# 11_FlashMemory.net
KiCad netlist of a schematic drawn in Altium Designer
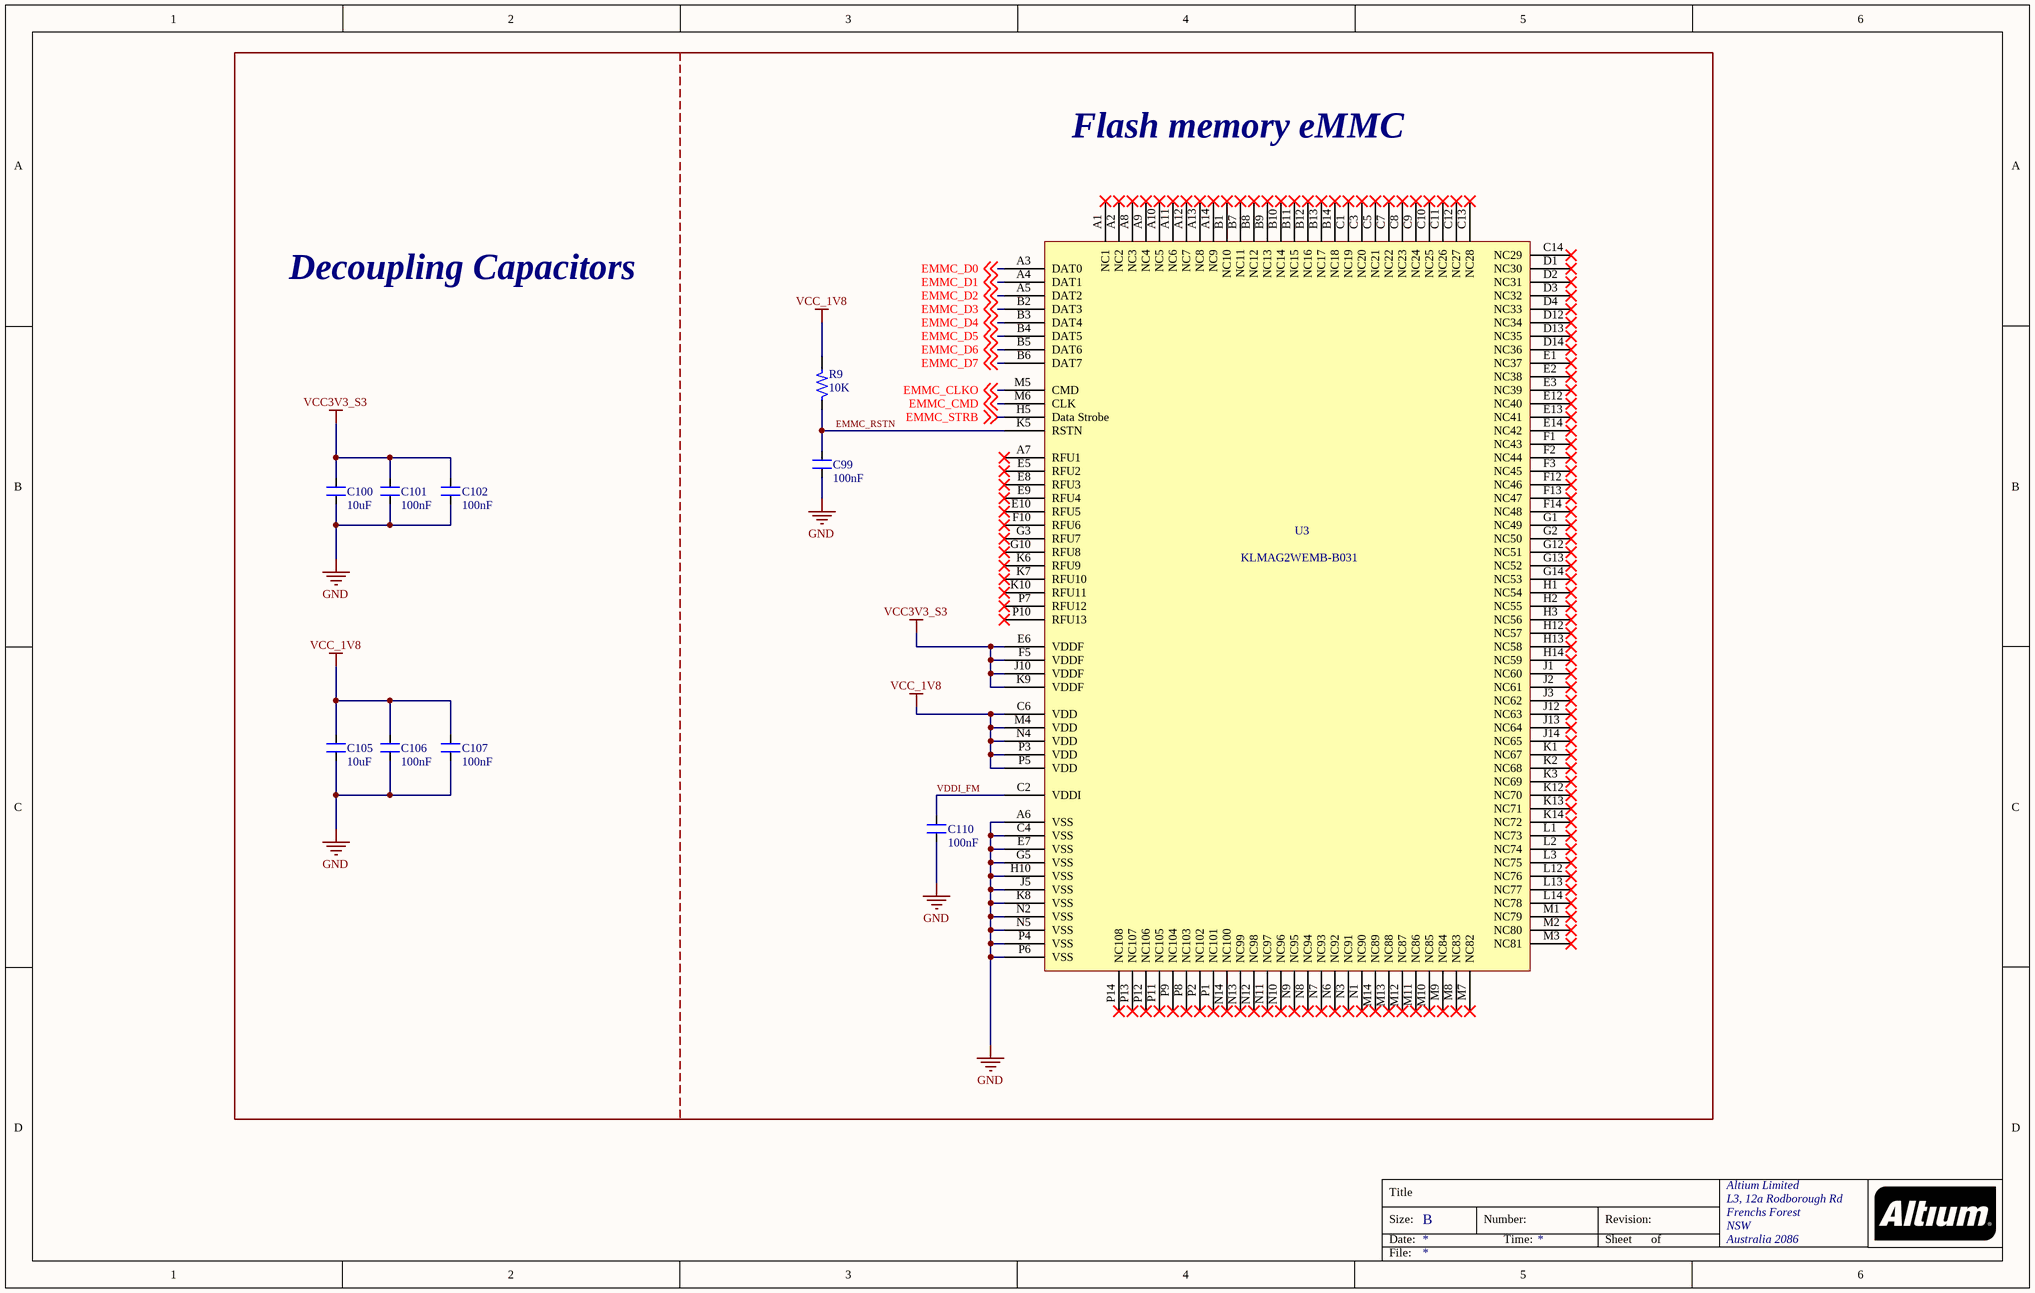
[diagram p0: [11] FlashMemory.SchDoc]

(export (version "E")
  (design (tool "Eeschema 10.0.6"))
  (components
    (comp (ref "C99")
      (value "100nF")
      (footprint "CAP_0201")
      (description "0.1µF ±10% 25V Ceramic Capacitor X5R 0201 (0603 Metric)")
      (fields
        (field (name "MANUFACTURER") "TDK Corporation")
        (field (name "MANUFACTURER PART NUMBER") "C0603X5R1E104K030BB")
      )
      (libsource (lib "EsteemPCB_SOM_Course_intlib") (part "CAP_100nF-25V-10%-0201"))
    )
    (comp (ref "C100")
      (value "10uF")
      (footprint "CAP_0603")
      (description "10µF ±10% 25V Ceramic Capacitor X5R 0603 (1608 Metric)")
      (fields
        (field (name "MANUFACTURER") "Murata Electronics")
        (field (name "MANUFACTURER PART NUMBER") "GRM188R61E106KA73D")
      )
      (libsource (lib "EsteemPCB_SOM_Course_intlib") (part "CAP_10uF-25V-10%-0603"))
    )
    (comp (ref "C101")
      (value "100nF")
      (footprint "CAP_0201")
      (description "0.1µF ±10% 25V Ceramic Capacitor X5R 0201 (0603 Metric)")
      (fields
        (field (name "MANUFACTURER") "TDK Corporation")
        (field (name "MANUFACTURER PART NUMBER") "C0603X5R1E104K030BB")
      )
      (libsource (lib "EsteemPCB_SOM_Course_intlib") (part "CAP_100nF-25V-10%-0201"))
    )
    (comp (ref "C102")
      (value "100nF")
      (footprint "CAP_0201")
      (description "0.1µF ±10% 25V Ceramic Capacitor X5R 0201 (0603 Metric)")
      (fields
        (field (name "MANUFACTURER") "TDK Corporation")
        (field (name "MANUFACTURER PART NUMBER") "C0603X5R1E104K030BB")
      )
      (libsource (lib "EsteemPCB_SOM_Course_intlib") (part "CAP_100nF-25V-10%-0201"))
    )
    (comp (ref "C105")
      (value "10uF")
      (footprint "CAP_0603")
      (description "10µF ±10% 25V Ceramic Capacitor X5R 0603 (1608 Metric)")
      (fields
        (field (name "MANUFACTURER") "Murata Electronics")
        (field (name "MANUFACTURER PART NUMBER") "GRM188R61E106KA73D")
      )
      (libsource (lib "EsteemPCB_SOM_Course_intlib") (part "CAP_10uF-25V-10%-0603"))
    )
    (comp (ref "C106")
      (value "100nF")
      (footprint "CAP_0201")
      (description "0.1µF ±10% 25V Ceramic Capacitor X5R 0201 (0603 Metric)")
      (fields
        (field (name "MANUFACTURER") "TDK Corporation")
        (field (name "MANUFACTURER PART NUMBER") "C0603X5R1E104K030BB")
      )
      (libsource (lib "EsteemPCB_SOM_Course_intlib") (part "CAP_100nF-25V-10%-0201"))
    )
    (comp (ref "C107")
      (value "100nF")
      (footprint "CAP_0201")
      (description "0.1µF ±10% 25V Ceramic Capacitor X5R 0201 (0603 Metric)")
      (fields
        (field (name "MANUFACTURER") "TDK Corporation")
        (field (name "MANUFACTURER PART NUMBER") "C0603X5R1E104K030BB")
      )
      (libsource (lib "EsteemPCB_SOM_Course_intlib") (part "CAP_100nF-25V-10%-0201"))
    )
    (comp (ref "C110")
      (value "100nF")
      (footprint "CAP_0201")
      (description "0.1µF ±10% 25V Ceramic Capacitor X5R 0201 (0603 Metric)")
      (fields
        (field (name "MANUFACTURER") "TDK Corporation")
        (field (name "MANUFACTURER PART NUMBER") "C0603X5R1E104K030BB")
      )
      (libsource (lib "EsteemPCB_SOM_Course_intlib") (part "CAP_100nF-25V-10%-0201"))
    )
    (comp (ref "R9")
      (value "10K")
      (footprint "RES_0201")
      (description "10 kOhms ±1% 0.05W, 1/20W Chip Resistor 0201 (0603 Metric) Thick Film")
      (fields
        (field (name "MANUFACTURER") "Stackpole Electronics Inc")
        (field (name "MANUFACTURER PART NUMBER") "RMCF0201FT10K0")
      )
      (libsource (lib "EsteemPCB_SOM_Course_intlib") (part "RES_10K-0.05W-1%-0201"))
    )
    (comp (ref "U3")
      (value "KLMAG2WEMB-B031")
      (footprint "BGA153C50P14X14_1150X1300X70")
      (description "16GB NAND Flash Memory")
      (fields (field (name "MANUFACTURER") "Samsung Electronics"))
      (libsource (lib "EsteemPCB_SOM_Course_intlib") (part "IC_KLMAG2WEMB-B031"))
    )
  )
  (nets
    (net (code "1") (name "/EMMC_RSTN") (class "Default")
      (node (ref "C99") (pin "2") (pinfunction "2_2") (pintype "passive"))
      (node (ref "R9") (pin "1") (pinfunction "1_1") (pintype "passive"))
      (node (ref "U3") (pin "K5") (pinfunction "RSTN_K5") (pintype "passive"))
    )
    (net (code "2") (name "/VDDI_FM") (class "Default")
      (node (ref "C110") (pin "2") (pinfunction "2_2") (pintype "passive"))
      (node (ref "U3") (pin "C2") (pinfunction "VDDI_C2") (pintype "passive"))
    )
    (net (code "3") (name "EMMC_CLKO") (class "Default")
      (node (ref "U3") (pin "M5") (pinfunction "CMD_M5") (pintype "passive"))
    )
    (net (code "4") (name "EMMC_CMD") (class "Default")
      (node (ref "U3") (pin "M6") (pinfunction "CLK_M6") (pintype "passive"))
    )
    (net (code "5") (name "EMMC_D0") (class "Default")
      (node (ref "U3") (pin "A3") (pinfunction "DAT0_A3") (pintype "passive"))
    )
    (net (code "6") (name "EMMC_D1") (class "Default")
      (node (ref "U3") (pin "A4") (pinfunction "DAT1_A4") (pintype "passive"))
    )
    (net (code "7") (name "EMMC_D2") (class "Default")
      (node (ref "U3") (pin "A5") (pinfunction "DAT2_A5") (pintype "passive"))
    )
    (net (code "8") (name "EMMC_D3") (class "Default")
      (node (ref "U3") (pin "B2") (pinfunction "DAT3_B2") (pintype "passive"))
    )
    (net (code "9") (name "EMMC_D4") (class "Default")
      (node (ref "U3") (pin "B3") (pinfunction "DAT4_B3") (pintype "passive"))
    )
    (net (code "10") (name "EMMC_D5") (class "Default")
      (node (ref "U3") (pin "B4") (pinfunction "DAT5_B4") (pintype "passive"))
    )
    (net (code "11") (name "EMMC_D6") (class "Default")
      (node (ref "U3") (pin "B5") (pinfunction "DAT6_B5") (pintype "passive"))
    )
    (net (code "12") (name "EMMC_D7") (class "Default")
      (node (ref "U3") (pin "B6") (pinfunction "DAT7_B6") (pintype "passive"))
    )
    (net (code "13") (name "EMMC_STRB") (class "Default")
      (node (ref "U3") (pin "H5") (pinfunction "Data_Strobe_H5") (pintype "passive"))
    )
    (net (code "14") (name "GND") (class "Default")
      (node (ref "C100") (pin "1") (pinfunction "1_1") (pintype "passive"))
      (node (ref "C101") (pin "1") (pinfunction "1_1") (pintype "passive"))
      (node (ref "C102") (pin "1") (pinfunction "1_1") (pintype "passive"))
      (node (ref "C105") (pin "1") (pinfunction "1_1") (pintype "passive"))
      (node (ref "C106") (pin "1") (pinfunction "1_1") (pintype "passive"))
      (node (ref "C107") (pin "1") (pinfunction "1_1") (pintype "passive"))
      (node (ref "C110") (pin "1") (pinfunction "1_1") (pintype "passive"))
      (node (ref "C99") (pin "1") (pinfunction "1_1") (pintype "passive"))
      (node (ref "U3") (pin "A6") (pinfunction "VSS_A6") (pintype "passive"))
      (node (ref "U3") (pin "C4") (pinfunction "VSS_C4") (pintype "passive"))
      (node (ref "U3") (pin "E7") (pinfunction "VSS_E7") (pintype "passive"))
      (node (ref "U3") (pin "G5") (pinfunction "VSS_G5") (pintype "passive"))
      (node (ref "U3") (pin "H10") (pinfunction "VSS_H10") (pintype "passive"))
      (node (ref "U3") (pin "J5") (pinfunction "VSS_J5") (pintype "passive"))
      (node (ref "U3") (pin "K8") (pinfunction "VSS_K8") (pintype "passive"))
      (node (ref "U3") (pin "N2") (pinfunction "VSS_N2") (pintype "passive"))
      (node (ref "U3") (pin "N5") (pinfunction "VSS_N5") (pintype "passive"))
      (node (ref "U3") (pin "P4") (pinfunction "VSS_P4") (pintype "passive"))
      (node (ref "U3") (pin "P6") (pinfunction "VSS_P6") (pintype "passive"))
    )
    (net (code "15") (name "VCC3V3_S3") (class "Default")
      (node (ref "C100") (pin "2") (pinfunction "2_2") (pintype "passive"))
      (node (ref "C101") (pin "2") (pinfunction "2_2") (pintype "passive"))
      (node (ref "C102") (pin "2") (pinfunction "2_2") (pintype "passive"))
      (node (ref "U3") (pin "E6") (pinfunction "VDDF_E6") (pintype "passive"))
      (node (ref "U3") (pin "F5") (pinfunction "VDDF_F5") (pintype "passive"))
      (node (ref "U3") (pin "J10") (pinfunction "VDDF_J10") (pintype "passive"))
      (node (ref "U3") (pin "K9") (pinfunction "VDDF_K9") (pintype "passive"))
    )
    (net (code "16") (name "VCC_1V8") (class "Default")
      (node (ref "C105") (pin "2") (pinfunction "2_2") (pintype "passive"))
      (node (ref "C106") (pin "2") (pinfunction "2_2") (pintype "passive"))
      (node (ref "C107") (pin "2") (pinfunction "2_2") (pintype "passive"))
      (node (ref "R9") (pin "2") (pinfunction "2_2") (pintype "passive"))
      (node (ref "U3") (pin "C6") (pinfunction "VDD_C6") (pintype "passive"))
      (node (ref "U3") (pin "M4") (pinfunction "VDD_M4") (pintype "passive"))
      (node (ref "U3") (pin "N4") (pinfunction "VDD_N4") (pintype "passive"))
      (node (ref "U3") (pin "P3") (pinfunction "VDD_P3") (pintype "passive"))
      (node (ref "U3") (pin "P5") (pinfunction "VDD_P5") (pintype "passive"))
    )
    (net (code "17") (name "unconnected-(U3-NC1-PadA1)") (class "Default")
      (node (ref "U3") (pin "A1") (pinfunction "NC1_A1") (pintype "passive+no_connect"))
    )
    (net (code "18") (name "unconnected-(U3-NC2-PadA2)") (class "Default")
      (node (ref "U3") (pin "A2") (pinfunction "NC2_A2") (pintype "passive+no_connect"))
    )
    (net (code "19") (name "unconnected-(U3-NC3-PadA8)") (class "Default")
      (node (ref "U3") (pin "A8") (pinfunction "NC3_A8") (pintype "passive+no_connect"))
    )
    (net (code "20") (name "unconnected-(U3-NC4-PadA9)") (class "Default")
      (node (ref "U3") (pin "A9") (pinfunction "NC4_A9") (pintype "passive+no_connect"))
    )
    (net (code "21") (name "unconnected-(U3-NC5-PadA10)") (class "Default")
      (node (ref "U3") (pin "A10") (pinfunction "NC5_A10") (pintype "passive+no_connect"))
    )
    (net (code "22") (name "unconnected-(U3-NC6-PadA11)") (class "Default")
      (node (ref "U3") (pin "A11") (pinfunction "NC6_A11") (pintype "passive+no_connect"))
    )
    (net (code "23") (name "unconnected-(U3-NC7-PadA12)") (class "Default")
      (node (ref "U3") (pin "A12") (pinfunction "NC7_A12") (pintype "passive+no_connect"))
    )
    (net (code "24") (name "unconnected-(U3-NC8-PadA13)") (class "Default")
      (node (ref "U3") (pin "A13") (pinfunction "NC8_A13") (pintype "passive+no_connect"))
    )
    (net (code "25") (name "unconnected-(U3-NC9-PadA14)") (class "Default")
      (node (ref "U3") (pin "A14") (pinfunction "NC9_A14") (pintype "passive+no_connect"))
    )
    (net (code "26") (name "unconnected-(U3-NC10-PadB1)") (class "Default")
      (node (ref "U3") (pin "B1") (pinfunction "NC10_B1") (pintype "passive+no_connect"))
    )
    (net (code "27") (name "unconnected-(U3-NC11-PadB7)") (class "Default")
      (node (ref "U3") (pin "B7") (pinfunction "NC11_B7") (pintype "passive+no_connect"))
    )
    (net (code "28") (name "unconnected-(U3-NC12-PadB8)") (class "Default")
      (node (ref "U3") (pin "B8") (pinfunction "NC12_B8") (pintype "passive+no_connect"))
    )
    (net (code "29") (name "unconnected-(U3-NC13-PadB9)") (class "Default")
      (node (ref "U3") (pin "B9") (pinfunction "NC13_B9") (pintype "passive+no_connect"))
    )
    (net (code "30") (name "unconnected-(U3-NC14-PadB10)") (class "Default")
      (node (ref "U3") (pin "B10") (pinfunction "NC14_B10") (pintype "passive+no_connect"))
    )
    (net (code "31") (name "unconnected-(U3-NC15-PadB11)") (class "Default")
      (node (ref "U3") (pin "B11") (pinfunction "NC15_B11") (pintype "passive+no_connect"))
    )
    (net (code "32") (name "unconnected-(U3-NC16-PadB12)") (class "Default")
      (node (ref "U3") (pin "B12") (pinfunction "NC16_B12") (pintype "passive+no_connect"))
    )
    (net (code "33") (name "unconnected-(U3-NC17-PadB13)") (class "Default")
      (node (ref "U3") (pin "B13") (pinfunction "NC17_B13") (pintype "passive+no_connect"))
    )
    (net (code "34") (name "unconnected-(U3-NC18-PadB14)") (class "Default")
      (node (ref "U3") (pin "B14") (pinfunction "NC18_B14") (pintype "passive+no_connect"))
    )
    (net (code "35") (name "unconnected-(U3-NC19-PadC1)") (class "Default")
      (node (ref "U3") (pin "C1") (pinfunction "NC19_C1") (pintype "passive+no_connect"))
    )
    (net (code "36") (name "unconnected-(U3-NC20-PadC3)") (class "Default")
      (node (ref "U3") (pin "C3") (pinfunction "NC20_C3") (pintype "passive+no_connect"))
    )
    (net (code "37") (name "unconnected-(U3-NC21-PadC5)") (class "Default")
      (node (ref "U3") (pin "C5") (pinfunction "NC21_C5") (pintype "passive+no_connect"))
    )
    (net (code "38") (name "unconnected-(U3-NC22-PadC7)") (class "Default")
      (node (ref "U3") (pin "C7") (pinfunction "NC22_C7") (pintype "passive+no_connect"))
    )
    (net (code "39") (name "unconnected-(U3-NC23-PadC8)") (class "Default")
      (node (ref "U3") (pin "C8") (pinfunction "NC23_C8") (pintype "passive+no_connect"))
    )
    (net (code "40") (name "unconnected-(U3-NC24-PadC9)") (class "Default")
      (node (ref "U3") (pin "C9") (pinfunction "NC24_C9") (pintype "passive+no_connect"))
    )
    (net (code "41") (name "unconnected-(U3-NC25-PadC10)") (class "Default")
      (node (ref "U3") (pin "C10") (pinfunction "NC25_C10") (pintype "passive+no_connect"))
    )
    (net (code "42") (name "unconnected-(U3-NC26-PadC11)") (class "Default")
      (node (ref "U3") (pin "C11") (pinfunction "NC26_C11") (pintype "passive+no_connect"))
    )
    (net (code "43") (name "unconnected-(U3-NC27-PadC12)") (class "Default")
      (node (ref "U3") (pin "C12") (pinfunction "NC27_C12") (pintype "passive+no_connect"))
    )
    (net (code "44") (name "unconnected-(U3-NC28-PadC13)") (class "Default")
      (node (ref "U3") (pin "C13") (pinfunction "NC28_C13") (pintype "passive+no_connect"))
    )
    (net (code "45") (name "unconnected-(U3-NC29-PadC14)") (class "Default")
      (node (ref "U3") (pin "C14") (pinfunction "NC29_C14") (pintype "passive+no_connect"))
    )
    (net (code "46") (name "unconnected-(U3-NC30-PadD1)") (class "Default")
      (node (ref "U3") (pin "D1") (pinfunction "NC30_D1") (pintype "passive+no_connect"))
    )
    (net (code "47") (name "unconnected-(U3-NC31-PadD2)") (class "Default")
      (node (ref "U3") (pin "D2") (pinfunction "NC31_D2") (pintype "passive+no_connect"))
    )
    (net (code "48") (name "unconnected-(U3-NC32-PadD3)") (class "Default")
      (node (ref "U3") (pin "D3") (pinfunction "NC32_D3") (pintype "passive+no_connect"))
    )
    (net (code "49") (name "unconnected-(U3-NC33-PadD4)") (class "Default")
      (node (ref "U3") (pin "D4") (pinfunction "NC33_D4") (pintype "passive+no_connect"))
    )
    (net (code "50") (name "unconnected-(U3-NC34-PadD12)") (class "Default")
      (node (ref "U3") (pin "D12") (pinfunction "NC34_D12") (pintype "passive+no_connect"))
    )
    (net (code "51") (name "unconnected-(U3-NC35-PadD13)") (class "Default")
      (node (ref "U3") (pin "D13") (pinfunction "NC35_D13") (pintype "passive+no_connect"))
    )
    (net (code "52") (name "unconnected-(U3-NC36-PadD14)") (class "Default")
      (node (ref "U3") (pin "D14") (pinfunction "NC36_D14") (pintype "passive+no_connect"))
    )
    (net (code "53") (name "unconnected-(U3-NC37-PadE1)") (class "Default")
      (node (ref "U3") (pin "E1") (pinfunction "NC37_E1") (pintype "passive+no_connect"))
    )
    (net (code "54") (name "unconnected-(U3-NC38-PadE2)") (class "Default")
      (node (ref "U3") (pin "E2") (pinfunction "NC38_E2") (pintype "passive+no_connect"))
    )
    (net (code "55") (name "unconnected-(U3-NC39-PadE3)") (class "Default")
      (node (ref "U3") (pin "E3") (pinfunction "NC39_E3") (pintype "passive+no_connect"))
    )
    (net (code "56") (name "unconnected-(U3-NC40-PadE12)") (class "Default")
      (node (ref "U3") (pin "E12") (pinfunction "NC40_E12") (pintype "passive+no_connect"))
    )
    (net (code "57") (name "unconnected-(U3-NC41-PadE13)") (class "Default")
      (node (ref "U3") (pin "E13") (pinfunction "NC41_E13") (pintype "passive+no_connect"))
    )
    (net (code "58") (name "unconnected-(U3-NC42-PadE14)") (class "Default")
      (node (ref "U3") (pin "E14") (pinfunction "NC42_E14") (pintype "passive+no_connect"))
    )
    (net (code "59") (name "unconnected-(U3-NC43-PadF1)") (class "Default")
      (node (ref "U3") (pin "F1") (pinfunction "NC43_F1") (pintype "passive+no_connect"))
    )
    (net (code "60") (name "unconnected-(U3-NC44-PadF2)") (class "Default")
      (node (ref "U3") (pin "F2") (pinfunction "NC44_F2") (pintype "passive+no_connect"))
    )
    (net (code "61") (name "unconnected-(U3-NC45-PadF3)") (class "Default")
      (node (ref "U3") (pin "F3") (pinfunction "NC45_F3") (pintype "passive+no_connect"))
    )
    (net (code "62") (name "unconnected-(U3-NC46-PadF12)") (class "Default")
      (node (ref "U3") (pin "F12") (pinfunction "NC46_F12") (pintype "passive+no_connect"))
    )
    (net (code "63") (name "unconnected-(U3-NC47-PadF13)") (class "Default")
      (node (ref "U3") (pin "F13") (pinfunction "NC47_F13") (pintype "passive+no_connect"))
    )
    (net (code "64") (name "unconnected-(U3-NC48-PadF14)") (class "Default")
      (node (ref "U3") (pin "F14") (pinfunction "NC48_F14") (pintype "passive+no_connect"))
    )
    (net (code "65") (name "unconnected-(U3-NC49-PadG1)") (class "Default")
      (node (ref "U3") (pin "G1") (pinfunction "NC49_G1") (pintype "passive+no_connect"))
    )
    (net (code "66") (name "unconnected-(U3-NC50-PadG2)") (class "Default")
      (node (ref "U3") (pin "G2") (pinfunction "NC50_G2") (pintype "passive+no_connect"))
    )
    (net (code "67") (name "unconnected-(U3-NC51-PadG12)") (class "Default")
      (node (ref "U3") (pin "G12") (pinfunction "NC51_G12") (pintype "passive+no_connect"))
    )
    (net (code "68") (name "unconnected-(U3-NC52-PadG13)") (class "Default")
      (node (ref "U3") (pin "G13") (pinfunction "NC52_G13") (pintype "passive+no_connect"))
    )
    (net (code "69") (name "unconnected-(U3-NC53-PadG14)") (class "Default")
      (node (ref "U3") (pin "G14") (pinfunction "NC53_G14") (pintype "passive+no_connect"))
    )
    (net (code "70") (name "unconnected-(U3-NC54-PadH1)") (class "Default")
      (node (ref "U3") (pin "H1") (pinfunction "NC54_H1") (pintype "passive+no_connect"))
    )
    (net (code "71") (name "unconnected-(U3-NC55-PadH2)") (class "Default")
      (node (ref "U3") (pin "H2") (pinfunction "NC55_H2") (pintype "passive+no_connect"))
    )
    (net (code "72") (name "unconnected-(U3-NC56-PadH3)") (class "Default")
      (node (ref "U3") (pin "H3") (pinfunction "NC56_H3") (pintype "passive+no_connect"))
    )
    (net (code "73") (name "unconnected-(U3-NC57-PadH12)") (class "Default")
      (node (ref "U3") (pin "H12") (pinfunction "NC57_H12") (pintype "passive+no_connect"))
    )
    (net (code "74") (name "unconnected-(U3-NC58-PadH13)") (class "Default")
      (node (ref "U3") (pin "H13") (pinfunction "NC58_H13") (pintype "passive+no_connect"))
    )
    (net (code "75") (name "unconnected-(U3-NC59-PadH14)") (class "Default")
      (node (ref "U3") (pin "H14") (pinfunction "NC59_H14") (pintype "passive+no_connect"))
    )
    (net (code "76") (name "unconnected-(U3-NC60-PadJ1)") (class "Default")
      (node (ref "U3") (pin "J1") (pinfunction "NC60_J1") (pintype "passive+no_connect"))
    )
    (net (code "77") (name "unconnected-(U3-NC61-PadJ2)") (class "Default")
      (node (ref "U3") (pin "J2") (pinfunction "NC61_J2") (pintype "passive+no_connect"))
    )
    (net (code "78") (name "unconnected-(U3-NC62-PadJ3)") (class "Default")
      (node (ref "U3") (pin "J3") (pinfunction "NC62_J3") (pintype "passive+no_connect"))
    )
    (net (code "79") (name "unconnected-(U3-NC63-PadJ12)") (class "Default")
      (node (ref "U3") (pin "J12") (pinfunction "NC63_J12") (pintype "passive+no_connect"))
    )
    (net (code "80") (name "unconnected-(U3-NC64-PadJ13)") (class "Default")
      (node (ref "U3") (pin "J13") (pinfunction "NC64_J13") (pintype "passive+no_connect"))
    )
    (net (code "81") (name "unconnected-(U3-NC65-PadJ14)") (class "Default")
      (node (ref "U3") (pin "J14") (pinfunction "NC65_J14") (pintype "passive+no_connect"))
    )
    (net (code "82") (name "unconnected-(U3-NC67-PadK1)") (class "Default")
      (node (ref "U3") (pin "K1") (pinfunction "NC67_K1") (pintype "passive+no_connect"))
    )
    (net (code "83") (name "unconnected-(U3-NC68-PadK2)") (class "Default")
      (node (ref "U3") (pin "K2") (pinfunction "NC68_K2") (pintype "passive+no_connect"))
    )
    (net (code "84") (name "unconnected-(U3-NC69-PadK3)") (class "Default")
      (node (ref "U3") (pin "K3") (pinfunction "NC69_K3") (pintype "passive+no_connect"))
    )
    (net (code "85") (name "unconnected-(U3-NC70-PadK12)") (class "Default")
      (node (ref "U3") (pin "K12") (pinfunction "NC70_K12") (pintype "passive+no_connect"))
    )
    (net (code "86") (name "unconnected-(U3-NC71-PadK13)") (class "Default")
      (node (ref "U3") (pin "K13") (pinfunction "NC71_K13") (pintype "passive+no_connect"))
    )
    (net (code "87") (name "unconnected-(U3-NC72-PadK14)") (class "Default")
      (node (ref "U3") (pin "K14") (pinfunction "NC72_K14") (pintype "passive+no_connect"))
    )
    (net (code "88") (name "unconnected-(U3-NC73-PadL1)") (class "Default")
      (node (ref "U3") (pin "L1") (pinfunction "NC73_L1") (pintype "passive+no_connect"))
    )
    (net (code "89") (name "unconnected-(U3-NC74-PadL2)") (class "Default")
      (node (ref "U3") (pin "L2") (pinfunction "NC74_L2") (pintype "passive+no_connect"))
    )
    (net (code "90") (name "unconnected-(U3-NC75-PadL3)") (class "Default")
      (node (ref "U3") (pin "L3") (pinfunction "NC75_L3") (pintype "passive+no_connect"))
    )
    (net (code "91") (name "unconnected-(U3-NC76-PadL12)") (class "Default")
      (node (ref "U3") (pin "L12") (pinfunction "NC76_L12") (pintype "passive+no_connect"))
    )
    (net (code "92") (name "unconnected-(U3-NC77-PadL13)") (class "Default")
      (node (ref "U3") (pin "L13") (pinfunction "NC77_L13") (pintype "passive+no_connect"))
    )
    (net (code "93") (name "unconnected-(U3-NC78-PadL14)") (class "Default")
      (node (ref "U3") (pin "L14") (pinfunction "NC78_L14") (pintype "passive+no_connect"))
    )
    (net (code "94") (name "unconnected-(U3-NC79-PadM1)") (class "Default")
      (node (ref "U3") (pin "M1") (pinfunction "NC79_M1") (pintype "passive+no_connect"))
    )
    (net (code "95") (name "unconnected-(U3-NC80-PadM2)") (class "Default")
      (node (ref "U3") (pin "M2") (pinfunction "NC80_M2") (pintype "passive+no_connect"))
    )
    (net (code "96") (name "unconnected-(U3-NC81-PadM3)") (class "Default")
      (node (ref "U3") (pin "M3") (pinfunction "NC81_M3") (pintype "passive+no_connect"))
    )
    (net (code "97") (name "unconnected-(U3-NC82-PadM7)") (class "Default")
      (node (ref "U3") (pin "M7") (pinfunction "NC82_M7") (pintype "passive+no_connect"))
    )
    (net (code "98") (name "unconnected-(U3-NC83-PadM8)") (class "Default")
      (node (ref "U3") (pin "M8") (pinfunction "NC83_M8") (pintype "passive+no_connect"))
    )
    (net (code "99") (name "unconnected-(U3-NC84-PadM9)") (class "Default")
      (node (ref "U3") (pin "M9") (pinfunction "NC84_M9") (pintype "passive+no_connect"))
    )
    (net (code "100") (name "unconnected-(U3-NC85-PadM10)") (class "Default")
      (node (ref "U3") (pin "M10") (pinfunction "NC85_M10") (pintype "passive+no_connect"))
    )
    (net (code "101") (name "unconnected-(U3-NC86-PadM11)") (class "Default")
      (node (ref "U3") (pin "M11") (pinfunction "NC86_M11") (pintype "passive+no_connect"))
    )
    (net (code "102") (name "unconnected-(U3-NC87-PadM12)") (class "Default")
      (node (ref "U3") (pin "M12") (pinfunction "NC87_M12") (pintype "passive+no_connect"))
    )
    (net (code "103") (name "unconnected-(U3-NC88-PadM13)") (class "Default")
      (node (ref "U3") (pin "M13") (pinfunction "NC88_M13") (pintype "passive+no_connect"))
    )
    (net (code "104") (name "unconnected-(U3-NC89-PadM14)") (class "Default")
      (node (ref "U3") (pin "M14") (pinfunction "NC89_M14") (pintype "passive+no_connect"))
    )
    (net (code "105") (name "unconnected-(U3-NC90-PadN1)") (class "Default")
      (node (ref "U3") (pin "N1") (pinfunction "NC90_N1") (pintype "passive+no_connect"))
    )
    (net (code "106") (name "unconnected-(U3-NC91-PadN3)") (class "Default")
      (node (ref "U3") (pin "N3") (pinfunction "NC91_N3") (pintype "passive+no_connect"))
    )
    (net (code "107") (name "unconnected-(U3-NC92-PadN6)") (class "Default")
      (node (ref "U3") (pin "N6") (pinfunction "NC92_N6") (pintype "passive+no_connect"))
    )
    (net (code "108") (name "unconnected-(U3-NC93-PadN7)") (class "Default")
      (node (ref "U3") (pin "N7") (pinfunction "NC93_N7") (pintype "passive+no_connect"))
    )
    (net (code "109") (name "unconnected-(U3-NC94-PadN8)") (class "Default")
      (node (ref "U3") (pin "N8") (pinfunction "NC94_N8") (pintype "passive+no_connect"))
    )
    (net (code "110") (name "unconnected-(U3-NC95-PadN9)") (class "Default")
      (node (ref "U3") (pin "N9") (pinfunction "NC95_N9") (pintype "passive+no_connect"))
    )
    (net (code "111") (name "unconnected-(U3-NC96-PadN10)") (class "Default")
      (node (ref "U3") (pin "N10") (pinfunction "NC96_N10") (pintype "passive+no_connect"))
    )
    (net (code "112") (name "unconnected-(U3-NC97-PadN11)") (class "Default")
      (node (ref "U3") (pin "N11") (pinfunction "NC97_N11") (pintype "passive+no_connect"))
    )
    (net (code "113") (name "unconnected-(U3-NC98-PadN12)") (class "Default")
      (node (ref "U3") (pin "N12") (pinfunction "NC98_N12") (pintype "passive+no_connect"))
    )
    (net (code "114") (name "unconnected-(U3-NC99-PadN13)") (class "Default")
      (node (ref "U3") (pin "N13") (pinfunction "NC99_N13") (pintype "passive+no_connect"))
    )
    (net (code "115") (name "unconnected-(U3-NC100-PadN14)") (class "Default")
      (node (ref "U3") (pin "N14") (pinfunction "NC100_N14") (pintype "passive+no_connect"))
    )
    (net (code "116") (name "unconnected-(U3-NC101-PadP1)") (class "Default")
      (node (ref "U3") (pin "P1") (pinfunction "NC101_P1") (pintype "passive+no_connect"))
    )
    (net (code "117") (name "unconnected-(U3-NC102-PadP2)") (class "Default")
      (node (ref "U3") (pin "P2") (pinfunction "NC102_P2") (pintype "passive+no_connect"))
    )
    (net (code "118") (name "unconnected-(U3-NC103-PadP8)") (class "Default")
      (node (ref "U3") (pin "P8") (pinfunction "NC103_P8") (pintype "passive+no_connect"))
    )
    (net (code "119") (name "unconnected-(U3-NC104-PadP9)") (class "Default")
      (node (ref "U3") (pin "P9") (pinfunction "NC104_P9") (pintype "passive+no_connect"))
    )
    (net (code "120") (name "unconnected-(U3-NC105-PadP11)") (class "Default")
      (node (ref "U3") (pin "P11") (pinfunction "NC105_P11") (pintype "passive+no_connect"))
    )
    (net (code "121") (name "unconnected-(U3-NC106-PadP12)") (class "Default")
      (node (ref "U3") (pin "P12") (pinfunction "NC106_P12") (pintype "passive+no_connect"))
    )
    (net (code "122") (name "unconnected-(U3-NC107-PadP13)") (class "Default")
      (node (ref "U3") (pin "P13") (pinfunction "NC107_P13") (pintype "passive+no_connect"))
    )
    (net (code "123") (name "unconnected-(U3-NC108-PadP14)") (class "Default")
      (node (ref "U3") (pin "P14") (pinfunction "NC108_P14") (pintype "passive+no_connect"))
    )
    (net (code "124") (name "unconnected-(U3-RFU1-PadA7)") (class "Default")
      (node (ref "U3") (pin "A7") (pinfunction "RFU1_A7") (pintype "passive+no_connect"))
    )
    (net (code "125") (name "unconnected-(U3-RFU2-PadE5)") (class "Default")
      (node (ref "U3") (pin "E5") (pinfunction "RFU2_E5") (pintype "passive+no_connect"))
    )
    (net (code "126") (name "unconnected-(U3-RFU3-PadE8)") (class "Default")
      (node (ref "U3") (pin "E8") (pinfunction "RFU3_E8") (pintype "passive+no_connect"))
    )
    (net (code "127") (name "unconnected-(U3-RFU4-PadE9)") (class "Default")
      (node (ref "U3") (pin "E9") (pinfunction "RFU4_E9") (pintype "passive+no_connect"))
    )
    (net (code "128") (name "unconnected-(U3-RFU5-PadE10)") (class "Default")
      (node (ref "U3") (pin "E10") (pinfunction "RFU5_E10") (pintype "passive+no_connect"))
    )
    (net (code "129") (name "unconnected-(U3-RFU6-PadF10)") (class "Default")
      (node (ref "U3") (pin "F10") (pinfunction "RFU6_F10") (pintype "passive+no_connect"))
    )
    (net (code "130") (name "unconnected-(U3-RFU7-PadG3)") (class "Default")
      (node (ref "U3") (pin "G3") (pinfunction "RFU7_G3") (pintype "passive+no_connect"))
    )
    (net (code "131") (name "unconnected-(U3-RFU8-PadG10)") (class "Default")
      (node (ref "U3") (pin "G10") (pinfunction "RFU8_G10") (pintype "passive+no_connect"))
    )
    (net (code "132") (name "unconnected-(U3-RFU9-PadK6)") (class "Default")
      (node (ref "U3") (pin "K6") (pinfunction "RFU9_K6") (pintype "passive+no_connect"))
    )
    (net (code "133") (name "unconnected-(U3-RFU10-PadK7)") (class "Default")
      (node (ref "U3") (pin "K7") (pinfunction "RFU10_K7") (pintype "passive+no_connect"))
    )
    (net (code "134") (name "unconnected-(U3-RFU11-PadK10)") (class "Default")
      (node (ref "U3") (pin "K10") (pinfunction "RFU11_K10") (pintype "passive+no_connect"))
    )
    (net (code "135") (name "unconnected-(U3-RFU12-PadP7)") (class "Default")
      (node (ref "U3") (pin "P7") (pinfunction "RFU12_P7") (pintype "passive+no_connect"))
    )
    (net (code "136") (name "unconnected-(U3-RFU13-PadP10)") (class "Default")
      (node (ref "U3") (pin "P10") (pinfunction "RFU13_P10") (pintype "passive+no_connect"))
    )
  )
)
